# USB_C_PD_Sink.net
KiCad netlist of a schematic drawn in Altium Designer
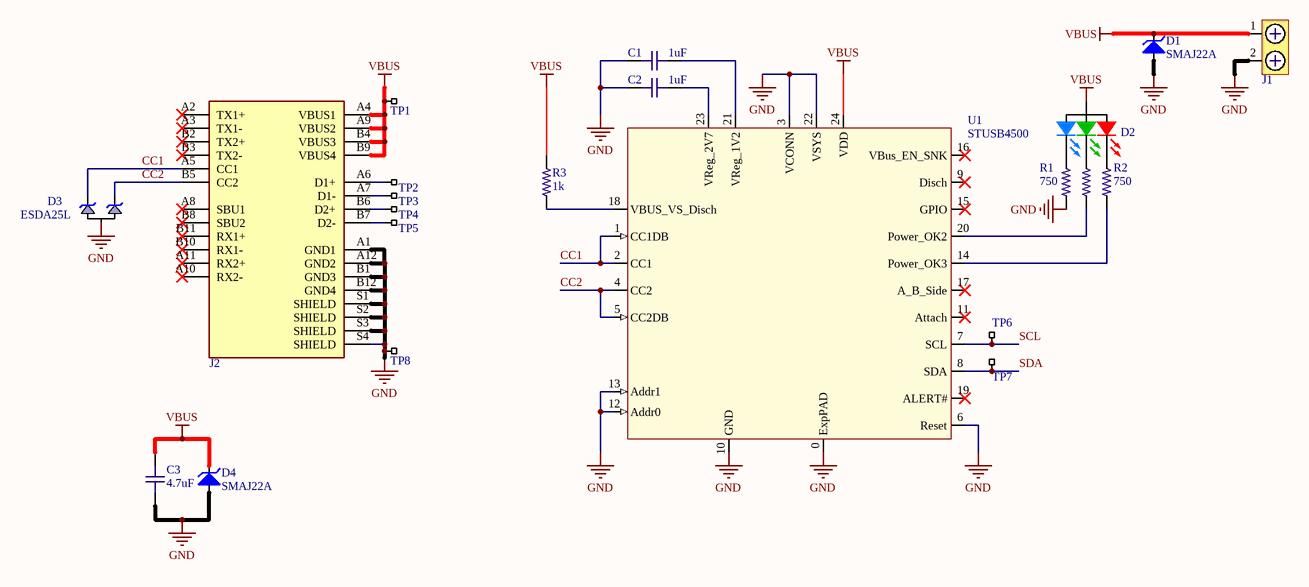
[diagram p0: USB_C_PD_Sink.SchDoc]

(export (version "E")
  (design (tool "Eeschema 10.0.6"))
  (components
    (comp (ref "C1")
      (value "1uF")
      (footprint "C0603-IPC")
      (description "Chip Capacitor, 0603, 1uF +/- 0.1uF, 10V, X7R")
      (fields (field (name "Comment") "C0603 1uF 10V X7R"))
      (libsource (lib "Capacitors") (part "C0603 1uF 10V X7R"))
    )
    (comp (ref "C2")
      (value "1uF")
      (footprint "C0603-IPC")
      (description "Chip Capacitor, 0603, 1uF +/- 0.1uF, 10V, X7R")
      (fields (field (name "Comment") "C0603 1uF 10V X7R"))
      (libsource (lib "Capacitors") (part "C0603 1uF 10V X7R"))
    )
    (comp (ref "C3")
      (value "4.7uF")
      (footprint "C0603-HIGH-DENSITY")
      (description "Chip Capacitor, 0603, 4.7uF, 25V, X5R")
      (fields (field (name "Comment") "4.7uF, 25V, X5R, 0603"))
      (libsource (lib "Capacitors") (part "C0603 4.7uF 25V X5R"))
    )
    (comp (ref "D1")
      (value "SMAJ22A")
      (footprint "DO-214AC")
      (description "Bidirectional TVS DIODE 22V 35.5V DO214AC")
      (fields (field (name "MANUFACTURER") "Littlefuse Inc."))
      (libsource (lib "Diodes") (part "SMAJ22A"))
    )
    (comp (ref "D2")
      (value "RGB")
      (footprint "Diodes:LED_0606_RGB_WURTH")
      (description "RGB Led 1.6 x 1.6 mm Diffused")
      (fields
        (field (name "MANUFACTURER") "Everlight")
        (field (name "MANUFACTURER PART NUMBER") "19-237/R6GHBHW-C01/2T")
      )
      (libsource (lib "Diodes") (part "Led_RGB_0606"))
    )
    (comp (ref "D3")
      (value "ESDA25L")
      (footprint "SOT23-3L")
      (description "Dual Transil Array For ESD Protection in SOT23-3 Vbr = 25V")
      (fields (field (name "MANUFACTURER") "STMicroelectronics"))
      (libsource (lib "Diodes") (part "ESDA25L"))
    )
    (comp (ref "D4")
      (value "SMAJ22A")
      (footprint "DO-214AC")
      (description "Bidirectional TVS DIODE 22V 35.5V DO214AC")
      (fields (field (name "MANUFACTURER") "Littlefuse Inc."))
      (libsource (lib "Diodes") (part "SMAJ22A"))
    )
    (comp (ref "J1")
      (value "Phoenix Contact 1935161")
      (footprint "Phoenix_1935161")
      (description "Terminal Block, 2 Position, 5mm pitch, 18A, 300V, 12-26 AWG")
      (fields
        (field (name "MANUFACTURER") "Phoenix Contact")
        (field (name "MANUFACTURER PART NUMBER") "1935161")
      )
      (libsource (lib "Connectors") (part "Term Block 2pos"))
    )
    (comp (ref "J2")
      (value "USB C")
      (footprint "Connectors:Molex USB-C")
      (fields
        (field (name "MF") "Molex")
        (field (name "DIGI-KEY_PART_NUMBER") "WM12856CT-ND")
        (field (name "MP") "1054500101")
      )
      (libsource (lib "Connectors") (part "USB C"))
    )
    (comp (ref "R1")
      (value "750")
      (footprint "R0805-High-Density")
      (description "Chip Resistor, 0603, 750 ohms, 0.5W")
      (fields (field (name "Comment") "R0805 750 5%"))
      (libsource (lib "Resistors") (part "R0603 750 1%"))
    )
    (comp (ref "R2")
      (value "750")
      (footprint "R0805-High-Density")
      (description "Chip Resistor, 0603, 750 ohms, 0.5W")
      (fields (field (name "Comment") "R0805 750 5%"))
      (libsource (lib "Resistors") (part "R0603 750 1%"))
    )
    (comp (ref "R3")
      (value "1k")
      (footprint "R0603-HIGH-DENSITY")
      (description "RES SMD 1K OHM 1% 1/10W 0603")
      (fields (field (name "TOLERANCE") "±1%") (field (name "Comment") "R0603 1K 1%"))
      (libsource (lib "Resistors") (part "R0603 1K 1%"))
    )
    (comp (ref "R4")
      (value "R0805 750 5%")
      (footprint "R0805-High-Density")
      (description "Chip Resistor, 0603, 750 ohms, 0.5W")
      (libsource (lib "Resistors") (part "R0603 750 1%"))
    )
    (comp (ref "TP1")
      (value "VBUS")
      (footprint "TESTPOINT_SMT")
      (description "SMT Test Point")
      (libsource (lib "Virtual Parts") (part "Testpoint_SMT"))
    )
    (comp (ref "TP2")
      (value "D1+")
      (footprint "TESTPOINT_SMT")
      (description "SMT Test Point")
      (libsource (lib "Virtual Parts") (part "Testpoint_SMT"))
    )
    (comp (ref "TP3")
      (value "D1-")
      (footprint "TESTPOINT_SMT")
      (description "SMT Test Point")
      (libsource (lib "Virtual Parts") (part "Testpoint_SMT"))
    )
    (comp (ref "TP4")
      (value "D2+")
      (footprint "TESTPOINT_SMT")
      (description "SMT Test Point")
      (libsource (lib "Virtual Parts") (part "Testpoint_SMT"))
    )
    (comp (ref "TP5")
      (value "D2-")
      (footprint "TESTPOINT_SMT")
      (description "SMT Test Point")
      (libsource (lib "Virtual Parts") (part "Testpoint_SMT"))
    )
    (comp (ref "TP6")
      (value "SCL")
      (footprint "TESTPOINT_SMT")
      (description "SMT Test Point")
      (libsource (lib "Virtual Parts") (part "Testpoint_SMT"))
    )
    (comp (ref "TP7")
      (value "SDA")
      (footprint "TESTPOINT_SMT")
      (description "SMT Test Point")
      (libsource (lib "Virtual Parts") (part "Testpoint_SMT"))
    )
    (comp (ref "TP8")
      (value "VBUS")
      (footprint "TESTPOINT_SMT")
      (description "SMT Test Point")
      (libsource (lib "Virtual Parts") (part "Testpoint_SMT"))
    )
    (comp (ref "U1")
      (value "STUSB4500")
      (footprint "Integrated Circuits:QFN24 - 4X4MM - PITCH 0.5MM - EXPOSEDPAD")
      (description "Standalone USB PD controller  with SINK auto-run mode in QFN24 4x4mm")
      (fields (field (name "MANUFACTURER") "STMicroelectronics"))
      (libsource (lib "Integrated Circuits") (part "STUSB4500QTR"))
    )
  )
  (nets
    (net (code "1") (name "/CC1") (class "Default")
      (node (ref "D3") (pin "2") (pinfunction "K2_2") (pintype "power_in"))
      (node (ref "J2") (pin "A5") (pinfunction "CC1_A5") (pintype "passive"))
      (node (ref "U1") (pin "1") (pinfunction "CC1DB_1") (pintype "input"))
      (node (ref "U1") (pin "2") (pinfunction "CC1_2") (pintype "bidirectional"))
    )
    (net (code "2") (name "/CC2") (class "Default")
      (node (ref "D3") (pin "1") (pinfunction "K1_1") (pintype "passive"))
      (node (ref "J2") (pin "B5") (pinfunction "CC2_B5") (pintype "passive"))
      (node (ref "U1") (pin "4") (pinfunction "CC2_4") (pintype "bidirectional"))
      (node (ref "U1") (pin "5") (pinfunction "CC2DB_5") (pintype "input"))
    )
    (net (code "3") (name "/SCL") (class "Default")
      (node (ref "TP6") (pin "1") (pinfunction "1_1") (pintype "passive"))
      (node (ref "U1") (pin "7") (pinfunction "SCL_7") (pintype "passive"))
    )
    (net (code "4") (name "/SDA") (class "Default")
      (node (ref "TP7") (pin "1") (pinfunction "1_1") (pintype "passive"))
      (node (ref "U1") (pin "8") (pinfunction "SDA_8") (pintype "passive"))
    )
    (net (code "5") (name "GND") (class "Default")
      (node (ref "C1") (pin "1") (pintype "passive"))
      (node (ref "C2") (pin "1") (pintype "passive"))
      (node (ref "C3") (pin "1") (pintype "passive"))
      (node (ref "D1") (pin "1") (pinfunction "A_1") (pintype "passive"))
      (node (ref "D3") (pin "3") (pinfunction "A_3") (pintype "passive"))
      (node (ref "D4") (pin "1") (pinfunction "A_1") (pintype "passive"))
      (node (ref "J1") (pin "2") (pintype "passive"))
      (node (ref "J2") (pin "A1") (pinfunction "GND1_A1") (pintype "passive"))
      (node (ref "J2") (pin "A12") (pinfunction "GND2_A12") (pintype "passive"))
      (node (ref "J2") (pin "B1") (pinfunction "GND3_B1") (pintype "passive"))
      (node (ref "J2") (pin "B12") (pinfunction "GND4_B12") (pintype "passive"))
      (node (ref "J2") (pin "S1") (pinfunction "SHIELD_S1") (pintype "passive"))
      (node (ref "J2") (pin "S2") (pinfunction "SHIELD_S2") (pintype "passive"))
      (node (ref "J2") (pin "S3") (pinfunction "SHIELD_S3") (pintype "passive"))
      (node (ref "J2") (pin "S4") (pinfunction "SHIELD_S4") (pintype "passive"))
      (node (ref "R1") (pin "1") (pintype "passive"))
      (node (ref "TP8") (pin "1") (pinfunction "1_1") (pintype "passive"))
      (node (ref "U1") (pin "0") (pinfunction "ExpPAD_0") (pintype "passive"))
      (node (ref "U1") (pin "10") (pinfunction "GND_10") (pintype "passive"))
      (node (ref "U1") (pin "12") (pinfunction "Addr0_12") (pintype "input"))
      (node (ref "U1") (pin "13") (pinfunction "Addr1_13") (pintype "input"))
      (node (ref "U1") (pin "22") (pinfunction "VSYS_22") (pintype "passive"))
      (node (ref "U1") (pin "3") (pinfunction "VCONN_3") (pintype "passive"))
      (node (ref "U1") (pin "6") (pinfunction "Reset_6") (pintype "passive"))
    )
    (net (code "6") (name "Net-(D2-PadBK)") (class "Default")
      (node (ref "D2") (pin "BK") (pinfunction "BK_BK") (pintype "passive"))
      (node (ref "R1") (pin "2") (pintype "passive"))
    )
    (net (code "7") (name "Net-(D2-PadGK)") (class "Default")
      (node (ref "D2") (pin "GK") (pinfunction "GK_GK") (pintype "passive"))
      (node (ref "R4") (pin "2") (pintype "passive"))
    )
    (net (code "8") (name "Net-(D2-PadRK)") (class "Default")
      (node (ref "D2") (pin "RK") (pinfunction "RK_RK") (pintype "passive"))
      (node (ref "R2") (pin "2") (pintype "passive"))
    )
    (net (code "9") (name "Net-(J2-D1+)") (class "Default")
      (node (ref "J2") (pin "A6") (pinfunction "D1+_A6") (pintype "passive"))
      (node (ref "TP2") (pin "1") (pinfunction "1_1") (pintype "passive"))
    )
    (net (code "10") (name "Net-(J2-D1-)") (class "Default")
      (node (ref "J2") (pin "A7") (pinfunction "D1-_A7") (pintype "passive"))
      (node (ref "TP3") (pin "1") (pinfunction "1_1") (pintype "passive"))
    )
    (net (code "11") (name "Net-(J2-D2+)") (class "Default")
      (node (ref "J2") (pin "B6") (pinfunction "D2+_B6") (pintype "passive"))
      (node (ref "TP4") (pin "1") (pinfunction "1_1") (pintype "passive"))
    )
    (net (code "12") (name "Net-(J2-D2-)") (class "Default")
      (node (ref "J2") (pin "B7") (pinfunction "D2-_B7") (pintype "passive"))
      (node (ref "TP5") (pin "1") (pinfunction "1_1") (pintype "passive"))
    )
    (net (code "13") (name "Net-(U1-Power_OK2)") (class "Default")
      (node (ref "R4") (pin "1") (pintype "passive"))
      (node (ref "U1") (pin "20") (pinfunction "Power_OK2_20") (pintype "open_collector"))
    )
    (net (code "14") (name "Net-(U1-Power_OK3)") (class "Default")
      (node (ref "R2") (pin "1") (pintype "passive"))
      (node (ref "U1") (pin "14") (pinfunction "Power_OK3_14") (pintype "open_collector"))
    )
    (net (code "15") (name "Net-(U1-VBUS_VS_Disch)") (class "Default")
      (node (ref "R3") (pin "1") (pintype "passive"))
      (node (ref "U1") (pin "18") (pinfunction "VBUS_VS_Disch_18") (pintype "passive"))
    )
    (net (code "16") (name "Net-(U1-VReg_1V2)") (class "Default")
      (node (ref "C1") (pin "2") (pintype "passive"))
      (node (ref "U1") (pin "21") (pinfunction "VReg_1V2_21") (pintype "passive"))
    )
    (net (code "17") (name "Net-(U1-VReg_2V7)") (class "Default")
      (node (ref "C2") (pin "2") (pintype "passive"))
      (node (ref "U1") (pin "23") (pinfunction "VReg_2V7_23") (pintype "passive"))
    )
    (net (code "18") (name "VBUS") (class "Default")
      (node (ref "C3") (pin "2") (pintype "passive"))
      (node (ref "D1") (pin "2") (pinfunction "K_2") (pintype "passive"))
      (node (ref "D2") (pin "A") (pinfunction "A_A") (pintype "passive"))
      (node (ref "D4") (pin "2") (pinfunction "K_2") (pintype "passive"))
      (node (ref "J1") (pin "1") (pintype "passive"))
      (node (ref "J2") (pin "A4") (pinfunction "VBUS1_A4") (pintype "passive"))
      (node (ref "J2") (pin "A9") (pinfunction "VBUS2_A9") (pintype "passive"))
      (node (ref "J2") (pin "B4") (pinfunction "VBUS3_B4") (pintype "passive"))
      (node (ref "J2") (pin "B9") (pinfunction "VBUS4_B9") (pintype "passive"))
      (node (ref "R3") (pin "2") (pintype "passive"))
      (node (ref "TP1") (pin "1") (pinfunction "1_1") (pintype "passive"))
      (node (ref "U1") (pin "24") (pinfunction "VDD_24") (pintype "passive"))
    )
    (net (code "19") (name "unconnected-(J2-RX1+-PadB11)") (class "Default")
      (node (ref "J2") (pin "B11") (pinfunction "RX1+_B11") (pintype "passive+no_connect"))
    )
    (net (code "20") (name "unconnected-(J2-RX1--PadB10)") (class "Default")
      (node (ref "J2") (pin "B10") (pinfunction "RX1-_B10") (pintype "passive+no_connect"))
    )
    (net (code "21") (name "unconnected-(J2-RX2+-PadA11)") (class "Default")
      (node (ref "J2") (pin "A11") (pinfunction "RX2+_A11") (pintype "passive+no_connect"))
    )
    (net (code "22") (name "unconnected-(J2-RX2--PadA10)") (class "Default")
      (node (ref "J2") (pin "A10") (pinfunction "RX2-_A10") (pintype "passive+no_connect"))
    )
    (net (code "23") (name "unconnected-(J2-SBU1-PadA8)") (class "Default")
      (node (ref "J2") (pin "A8") (pinfunction "SBU1_A8") (pintype "passive+no_connect"))
    )
    (net (code "24") (name "unconnected-(J2-SBU2-PadB8)") (class "Default")
      (node (ref "J2") (pin "B8") (pinfunction "SBU2_B8") (pintype "passive+no_connect"))
    )
    (net (code "25") (name "unconnected-(J2-TX1+-PadA2)") (class "Default")
      (node (ref "J2") (pin "A2") (pinfunction "TX1+_A2") (pintype "passive+no_connect"))
    )
    (net (code "26") (name "unconnected-(J2-TX1--PadA3)") (class "Default")
      (node (ref "J2") (pin "A3") (pinfunction "TX1-_A3") (pintype "passive+no_connect"))
    )
    (net (code "27") (name "unconnected-(J2-TX2+-PadB2)") (class "Default")
      (node (ref "J2") (pin "B2") (pinfunction "TX2+_B2") (pintype "passive+no_connect"))
    )
    (net (code "28") (name "unconnected-(J2-TX2--PadB3)") (class "Default")
      (node (ref "J2") (pin "B3") (pinfunction "TX2-_B3") (pintype "passive+no_connect"))
    )
    (net (code "29") (name "unconnected-(U1-ALERT#-Pad19)") (class "Default")
      (node (ref "U1") (pin "19") (pinfunction "ALERT#_19") (pintype "open_collector+no_connect"))
    )
    (net (code "30") (name "unconnected-(U1-A_B_Side-Pad17)") (class "Default")
      (node (ref "U1") (pin "17") (pinfunction "A_B_Side_17") (pintype "open_collector+no_connect"))
    )
    (net (code "31") (name "unconnected-(U1-Attach-Pad11)") (class "Default")
      (node (ref "U1") (pin "11") (pinfunction "Attach_11") (pintype "open_collector+no_connect"))
    )
    (net (code "32") (name "unconnected-(U1-Disch-Pad9)") (class "Default")
      (node (ref "U1") (pin "9") (pinfunction "Disch_9") (pintype "open_collector+no_connect"))
    )
    (net (code "33") (name "unconnected-(U1-GPIO-Pad15)") (class "Default")
      (node (ref "U1") (pin "15") (pinfunction "GPIO_15") (pintype "open_collector+no_connect"))
    )
    (net (code "34") (name "unconnected-(U1-VBus_EN_SNK-Pad16)") (class "Default")
      (node (ref "U1") (pin "16") (pinfunction "VBus_EN_SNK_16") (pintype "open_collector+no_connect"))
    )
  )
)
